# SOM.net
KiCad netlist of a schematic drawn in Altium Designer
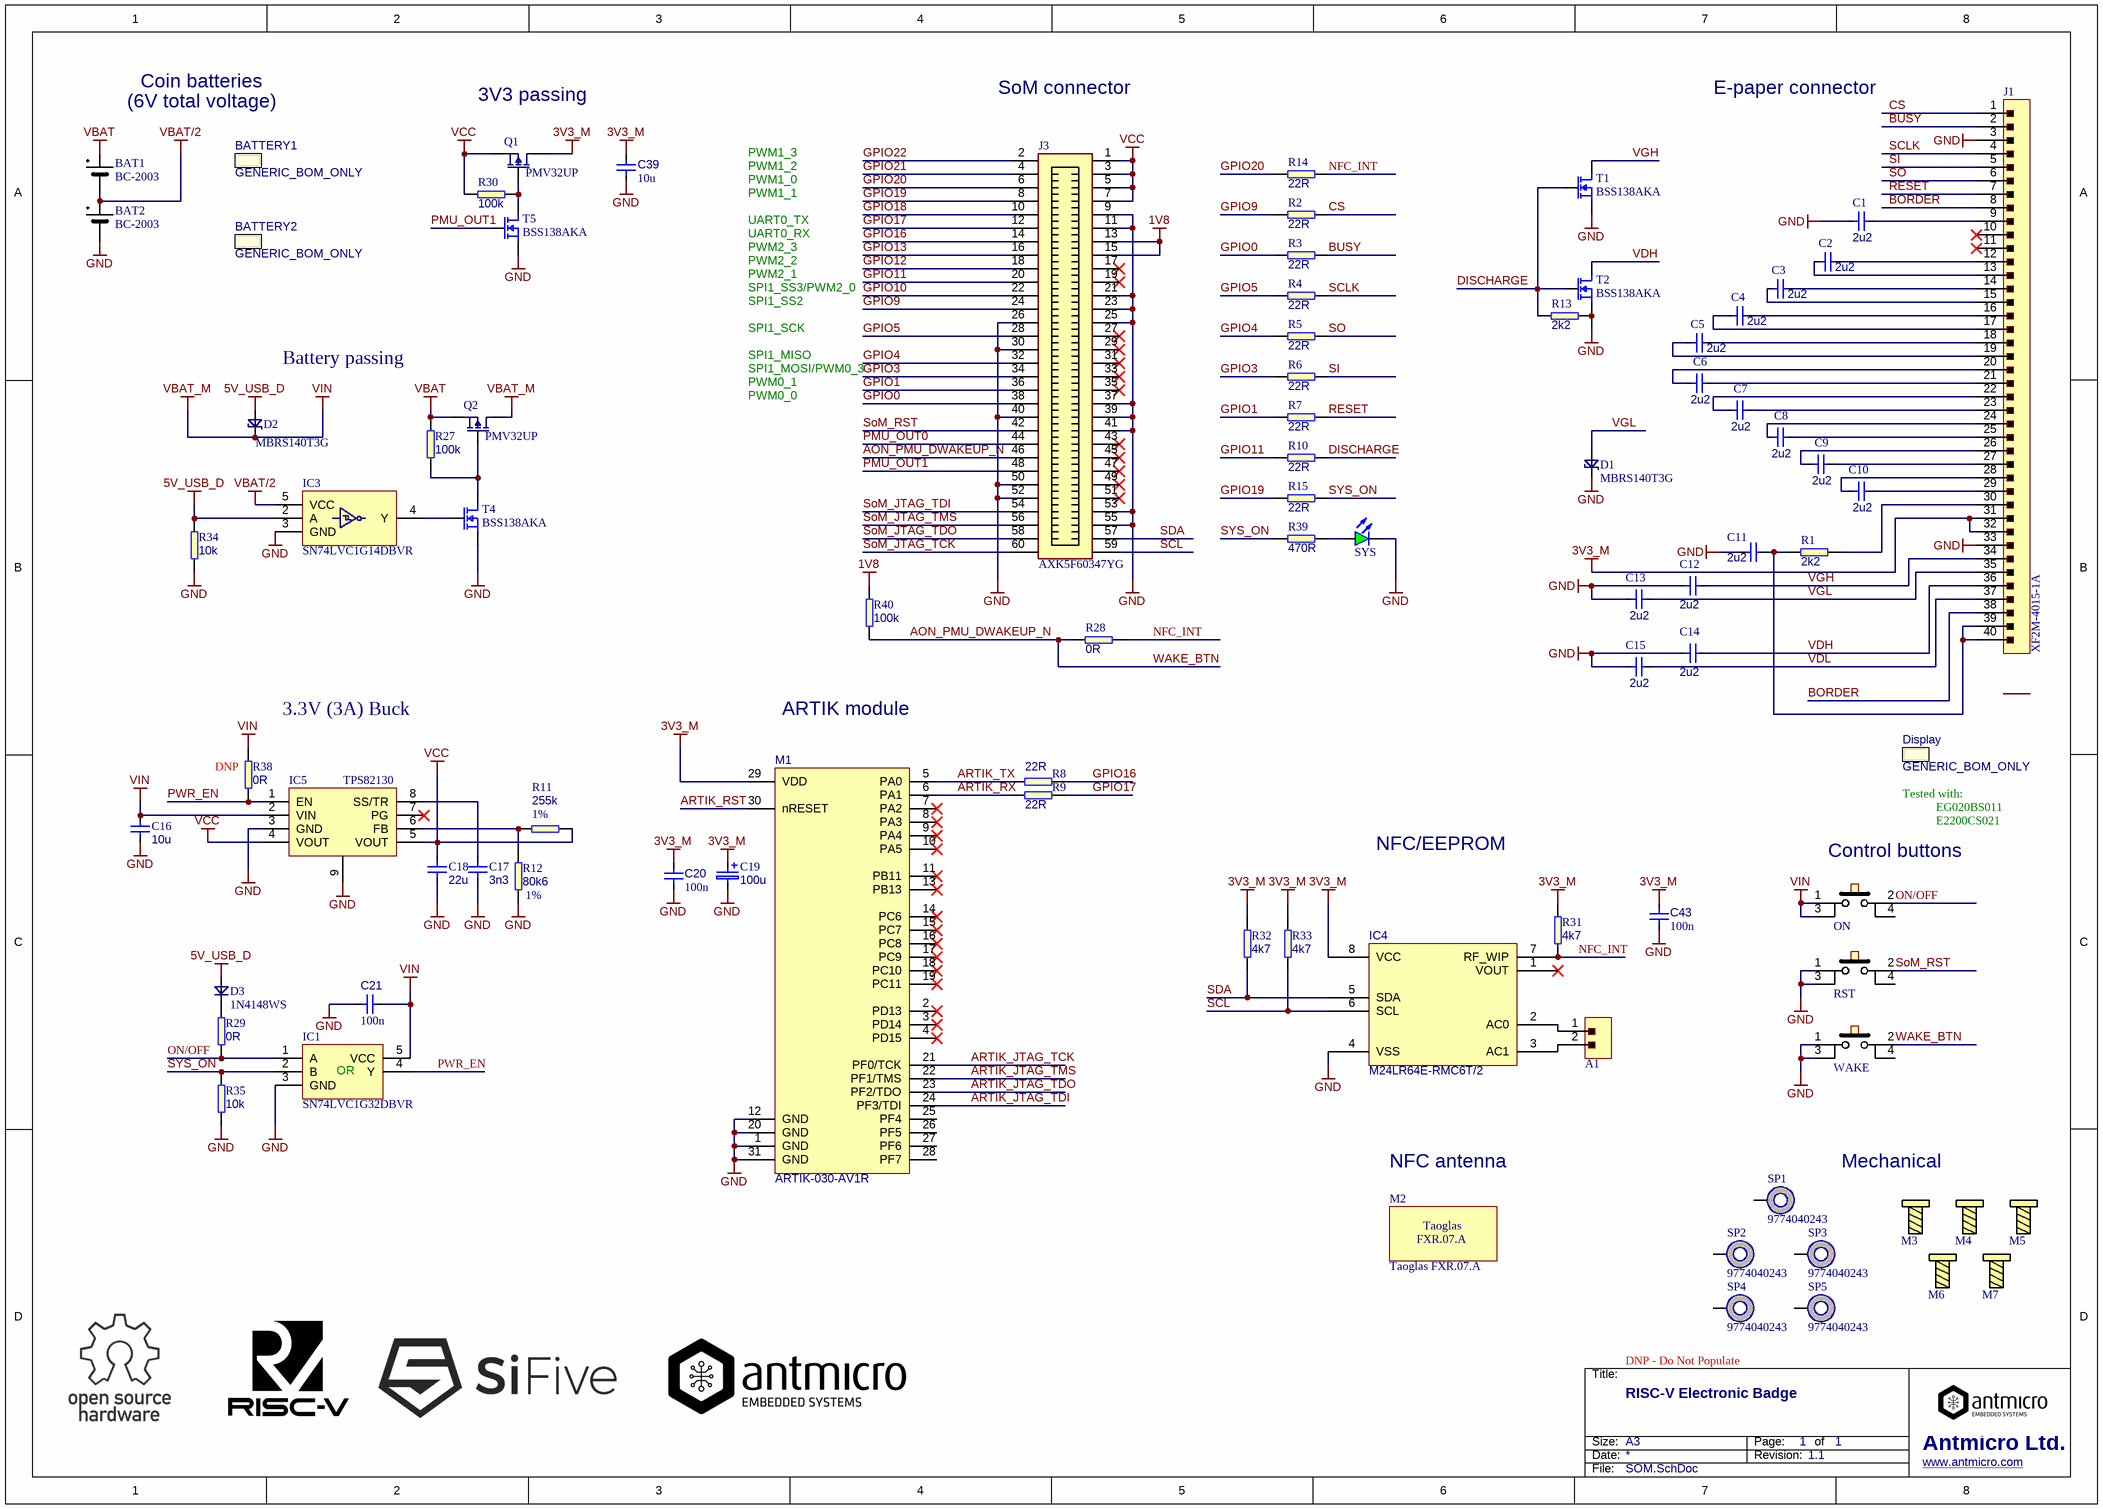
[diagram p0: SOM.SchDoc]

(export (version "E")
  (design (tool "Eeschema 10.0.6"))
  (components
    (comp (ref "A1")
      (value "811-22-002-30-001101")
      (footprint "812-22-002-30-003101")
      (description "Headers & Wire Housings 2P SINGLE ROW HDR .177\" PIN HEIGHT")
      (fields (field (name "MANUFACTURER") "MILL_MAX"))
      (libsource (lib "FE310_Badge") (part "1X02"))
    )
    (comp (ref "BAT1")
      (value "BC-2003")
      (footprint "BC-2003")
      (description "SMT holder for  CR2032 battery")
      (fields (field (name "MANUFACTURER") "Keystone"))
      (libsource (lib "FE310_Badge") (part "battery"))
    )
    (comp (ref "BAT2")
      (value "BC-2003")
      (footprint "BC-2003")
      (description "SMT holder for  CR2032 battery")
      (fields (field (name "MANUFACTURER") "Keystone"))
      (libsource (lib "FE310_Badge") (part "battery"))
    )
    (comp (ref "BATTERY1")
      (value "GENERIC_BOM_ONLY")
      (description "BOM Only")
      (fields (field (name "MANUFACTURER") "Pervasive Displays"))
      (libsource (lib "FE310_Badge") (part "GENERIC_BOM_ONLY"))
    )
    (comp (ref "BATTERY2")
      (value "GENERIC_BOM_ONLY")
      (description "BOM Only")
      (fields (field (name "MANUFACTURER") "Pervasive Displays"))
      (libsource (lib "FE310_Badge") (part "GENERIC_BOM_ONLY"))
    )
    (comp (ref "C1")
      (value "2u2")
      (footprint "0402")
      (description "MLCC SMT Capacitor 2u2 0402")
      (fields (field (name "PART NUMBER") "C_2u2_0402") (field (name "MANUFACTURER") "TDK"))
      (libsource (lib "FE310_Badge") (part "C_2u2_0402"))
    )
    (comp (ref "C2")
      (value "2u2")
      (footprint "0603")
      (description "MLCC SMT Capacitor 2u2 0603")
      (fields (field (name "PART NUMBER") "C_2u2_0603") (field (name "MANUFACTURER") "TDK"))
      (libsource (lib "FE310_Badge") (part "C_2u2_0603"))
    )
    (comp (ref "C3")
      (value "2u2")
      (footprint "0603")
      (description "MLCC SMT Capacitor 2u2 0603")
      (fields (field (name "PART NUMBER") "C_2u2_0603") (field (name "MANUFACTURER") "TDK"))
      (libsource (lib "FE310_Badge") (part "C_2u2_0603"))
    )
    (comp (ref "C4")
      (value "2u2")
      (footprint "0603")
      (description "MLCC SMT Capacitor 2u2 0603")
      (fields (field (name "PART NUMBER") "C_2u2_0603") (field (name "MANUFACTURER") "TDK"))
      (libsource (lib "FE310_Badge") (part "C_2u2_0603"))
    )
    (comp (ref "C5")
      (value "2u2")
      (footprint "0603")
      (description "MLCC SMT Capacitor 2u2 0603")
      (fields (field (name "PART NUMBER") "C_2u2_0603") (field (name "MANUFACTURER") "TDK"))
      (libsource (lib "FE310_Badge") (part "C_2u2_0603"))
    )
    (comp (ref "C6")
      (value "2u2")
      (footprint "0603")
      (description "MLCC SMT Capacitor 2u2 0603")
      (fields (field (name "PART NUMBER") "C_2u2_0603") (field (name "MANUFACTURER") "TDK"))
      (libsource (lib "FE310_Badge") (part "C_2u2_0603"))
    )
    (comp (ref "C7")
      (value "2u2")
      (footprint "0603")
      (description "MLCC SMT Capacitor 2u2 0603")
      (fields (field (name "PART NUMBER") "C_2u2_0603") (field (name "MANUFACTURER") "TDK"))
      (libsource (lib "FE310_Badge") (part "C_2u2_0603"))
    )
    (comp (ref "C8")
      (value "2u2")
      (footprint "0603")
      (description "MLCC SMT Capacitor 2u2 0603")
      (fields (field (name "PART NUMBER") "C_2u2_0603") (field (name "MANUFACTURER") "TDK"))
      (libsource (lib "FE310_Badge") (part "C_2u2_0603"))
    )
    (comp (ref "C9")
      (value "2u2")
      (footprint "0603")
      (description "MLCC SMT Capacitor 2u2 0603")
      (fields (field (name "PART NUMBER") "C_2u2_0603") (field (name "MANUFACTURER") "TDK"))
      (libsource (lib "FE310_Badge") (part "C_2u2_0603"))
    )
    (comp (ref "C10")
      (value "2u2")
      (footprint "0603")
      (description "MLCC SMT Capacitor 2u2 0603")
      (fields (field (name "PART NUMBER") "C_2u2_0603") (field (name "MANUFACTURER") "TDK"))
      (libsource (lib "FE310_Badge") (part "C_2u2_0603"))
    )
    (comp (ref "C11")
      (value "2u2")
      (footprint "0402")
      (description "MLCC SMT Capacitor 1u 0402")
      (fields (field (name "PART NUMBER") "C_2u2_0603") (field (name "MANUFACTURER") "MURATA"))
      (libsource (lib "FE310_Badge") (part "C_1u_0402"))
    )
    (comp (ref "C12")
      (value "2u2")
      (footprint "0603")
      (description "MLCC SMT Capacitor 2u2 0603")
      (fields (field (name "PART NUMBER") "C_2u2_0603") (field (name "MANUFACTURER") "TDK"))
      (libsource (lib "FE310_Badge") (part "C_2u2_0603"))
    )
    (comp (ref "C13")
      (value "2u2")
      (footprint "0603")
      (description "MLCC SMT Capacitor 2u2 0603")
      (fields (field (name "PART NUMBER") "C_2u2_0603") (field (name "MANUFACTURER") "TDK"))
      (libsource (lib "FE310_Badge") (part "C_2u2_0603"))
    )
    (comp (ref "C14")
      (value "2u2")
      (footprint "0603")
      (description "MLCC SMT Capacitor 2u2 0603")
      (fields (field (name "PART NUMBER") "C_2u2_0603") (field (name "MANUFACTURER") "TDK"))
      (libsource (lib "FE310_Badge") (part "C_2u2_0603"))
    )
    (comp (ref "C15")
      (value "2u2")
      (footprint "0603")
      (description "MLCC SMT Capacitor 2u2 0603")
      (fields (field (name "PART NUMBER") "C_2u2_0603") (field (name "MANUFACTURER") "TDK"))
      (libsource (lib "FE310_Badge") (part "C_2u2_0603"))
    )
    (comp (ref "C16")
      (value "10u")
      (footprint "0805")
      (description "MLCC SMT Capacitor 10u 0805")
      (fields (field (name "PART NUMBER") "C_10u_0805") (field (name "MANUFACTURER") "WALSIN"))
      (libsource (lib "FE310_Badge") (part "C_10u_0805"))
    )
    (comp (ref "C17")
      (value "3n3")
      (footprint "0603")
      (description "MLCC SMT Capacitor 3n3 0603")
      (fields (field (name "PART NUMBER") "C_3n3_0603") (field (name "MANUFACTURER") "WALSIN"))
      (libsource (lib "FE310_Badge") (part "C_3n3_0603"))
    )
    (comp (ref "C18")
      (value "22u")
      (footprint "0805")
      (description "MLCC SMT Capacitor 22u 0805")
      (fields (field (name "PART NUMBER") "C_22u_0805") (field (name "MANUFACTURER") "MULTICOMP"))
      (libsource (lib "FE310_Badge") (part "C_22u_0805"))
    )
    (comp (ref "C19")
      (value "100u")
      (footprint "KEMET_A")
      (description "Tantalum SMT Capacitor 100uF Case KEMET_A")
      (fields (field (name "PART NUMBER") "C_100u_KEMET_A") (field (name "MANUFACTURER") "VISHAY"))
      (libsource (lib "FE310_Badge") (part "CPol_100u"))
    )
    (comp (ref "C20")
      (value "100n")
      (footprint "0603")
      (description "MLCC SMT Capacitor 100nF 0603")
      (fields (field (name "PART NUMBER") "C_100n_0603") (field (name "MANUFACTURER") "WALSIN"))
      (libsource (lib "FE310_Badge") (part "C_100n_0603"))
    )
    (comp (ref "C21")
      (value "100n")
      (footprint "0402")
      (description "MLCC SMT Capacitor 100nF 0402")
      (fields (field (name "PART NUMBER") "C_100n_0402") (field (name "MANUFACTURER") "MULTICOMP"))
      (libsource (lib "FE310_Badge") (part "C_100n_0402"))
    )
    (comp (ref "C39")
      (value "10u")
      (footprint "0402")
      (description "MLCC SMT Capacitor 10uF 0402")
      (fields (field (name "PART NUMBER") "C_10u_0402") (field (name "MANUFACTURER") "TDK"))
      (libsource (lib "FE310_Badge") (part "C_10u_0402"))
    )
    (comp (ref "C43")
      (value "100n")
      (footprint "0402")
      (description "MLCC SMT Capacitor 100nF 0402")
      (fields (field (name "PART NUMBER") "C_100n_0402") (field (name "MANUFACTURER") "MULTICOMP"))
      (libsource (lib "FE310_Badge") (part "C_100n_0402"))
    )
    (comp (ref "D1")
      (value "MBRS140T3G")
      (footprint "SMB")
      (description "DIODE, SCHOTTKY, 1A, 40V, DO-214AA")
      (fields (field (name "MANUFACTURER") "ON SEMICONDUCTOR"))
      (libsource (lib "FE310_Badge") (part "Diode Schottky"))
    )
    (comp (ref "D2")
      (value "MBRS140T3G")
      (footprint "SMB")
      (description "DIODE, SCHOTTKY, 1A, 40V, DO-214AA")
      (fields (field (name "MANUFACTURER") "ON SEMICONDUCTOR"))
      (libsource (lib "FE310_Badge") (part "Diode Schottky"))
    )
    (comp (ref "D3")
      (value "1N4148WS")
      (footprint "SOD-323")
      (description "Diode small signal")
      (fields (field (name "MANUFACTURER") "MULTICOMP"))
      (libsource (lib "FE310_Badge") (part "diode"))
    )
    (comp (ref "Display")
      (value "GENERIC_BOM_ONLY")
      (description "BOM Only")
      (fields (field (name "MANUFACTURER") "Pervasive Displays"))
      (libsource (lib "FE310_Badge") (part "GENERIC_BOM_ONLY"))
    )
    (comp (ref "IC1")
      (value "SN74LVC1G32DBVR")
      (footprint "SOT23-5")
      (description "Single 2-Input OR Gate")
      (fields (field (name "MANUFACTURER") "TEXAS INSTRUMENTS"))
      (libsource (lib "FE310_Badge") (part "SN74LVC1G32DBVR"))
    )
    (comp (ref "IC3")
      (value "SN74LVC1G14DBVR")
      (footprint "SOT23-5")
      (description "Inverter with schmitt trigger.")
      (fields (field (name "MANUFACTURER") "TEXAS INSTRUMENTS"))
      (libsource (lib "FE310_Badge") (part "SN74LVC1G14"))
    )
    (comp (ref "IC4")
      (value "M24LR64E-RMC6T/2")
      (footprint "UFDFPN-8")
      (description "RFID Transponder IC 13.56MHz ISO 14443, NFC I²C 2.7 V ~ 5.5 V 8-UFDFN Exposed Pad")
      (fields (field (name "MANUFACTURER") "STMicroelectronics"))
      (libsource (lib "FE310_Badge") (part "M24LR04E_R"))
    )
    (comp (ref "IC5")
      (value "TPS82130")
      (footprint "MicroSIP")
      (fields (field (name "MANUFACTURER") "TEXAS INSTRUMENTS"))
      (libsource (lib "FE310_Badge") (part "TPS82130"))
    )
    (comp (ref "J1")
      (value "XF2M-4015-1A")
      (footprint "XF2M-4015-1A")
      (description "RECEPTACLE, FPC, ZIF, SMT, 0.5MM, 40WAY")
      (fields (field (name "MANUFACTURER") "OMRON ELECTRONIC COMPONENTS"))
      (libsource (lib "FE310_Badge") (part "XF2M-4015-1A"))
    )
    (comp (ref "J3")
      (value "AXK5F60347YG")
      (footprint "AXK5F60347YG")
      (description "CONN SCKT BRD/BRD .5MM 60POS SMD")
      (fields (field (name "MANUFACTURER") "PANASONIC"))
      (libsource (lib "FE310_Badge") (part "AXK5F60347YG"))
    )
    (comp (ref "M1")
      (value "ARTIK-030-AV1R")
      (footprint "ARTIK-030")
      (fields (field (name "PART NUMBER") "ARTIK-030") (field (name "MANUFACTURER") "Samsung"))
      (libsource (lib "FE310_Badge") (part "ARTIK-030"))
    )
    (comp (ref "M2")
      (value "Taoglas FXR.07.A")
      (description "ANT NFC FLEX CIRC 45.5X0.24MM")
      (fields (field (name "PART NUMBER") "taoglas") (field (name "MANUFACTURER") "TAOGLAS LIMITED"))
      (libsource (lib "FE310_Badge") (part "taoglas"))
    )
    (comp (ref "M3")
      (value "M2x5")
      (description "MACHINE SCREW PAN PHILLIPS M2")
      (fields
        (field (name "PART NUMBER") "MPMS 002 0005 PH")
        (field (name "MANUFACTURER") "B&F Fastener Supply")
      )
      (libsource (lib "FE310_Badge") (part "screw"))
    )
    (comp (ref "M4")
      (value "M2x5")
      (description "MACHINE SCREW PAN PHILLIPS M2")
      (fields
        (field (name "PART NUMBER") "MPMS 002 0005 PH")
        (field (name "MANUFACTURER") "B&F Fastener Supply")
      )
      (libsource (lib "FE310_Badge") (part "screw"))
    )
    (comp (ref "M5")
      (value "M2x5")
      (description "MACHINE SCREW PAN PHILLIPS M2")
      (fields
        (field (name "PART NUMBER") "MPMS 002 0005 PH")
        (field (name "MANUFACTURER") "B&F Fastener Supply")
      )
      (libsource (lib "FE310_Badge") (part "screw"))
    )
    (comp (ref "M6")
      (value "M2x5")
      (description "MACHINE SCREW PAN PHILLIPS M2")
      (fields
        (field (name "PART NUMBER") "MPMS 002 0005 PH")
        (field (name "MANUFACTURER") "B&F Fastener Supply")
      )
      (libsource (lib "FE310_Badge") (part "screw"))
    )
    (comp (ref "M7")
      (value "M2x5")
      (description "MACHINE SCREW PAN PHILLIPS M2")
      (fields
        (field (name "PART NUMBER") "MPMS 002 0005 PH")
        (field (name "MANUFACTURER") "B&F Fastener Supply")
      )
      (libsource (lib "FE310_Badge") (part "screw"))
    )
    (comp (ref "ON")
      (value "434333045822")
      (footprint "434333045822")
      (description "3.5x4.7 mm SMD side push, boss design WS-TASU")
      (fields (field (name "PART NUMBER") "WE_434333045822") (field (name "MANUFACTURER") "WURTH ELEKTRONIK"))
      (libsource (lib "FE310_Badge") (part "WE_434333045822"))
    )
    (comp (ref "Q1")
      (value "PMV32UP")
      (footprint "SOT-23")
      (description "P CH, 20V, 4A")
      (fields (field (name "MANUFACTURER") "NXP"))
      (libsource (lib "FE310_Badge") (part "PMOS"))
    )
    (comp (ref "Q2")
      (value "PMV32UP")
      (footprint "SOT-23")
      (description "P CH, 20V, 4A")
      (fields (field (name "MANUFACTURER") "NXP"))
      (libsource (lib "FE310_Badge") (part "PMOS"))
    )
    (comp (ref "R1")
      (value "2k2")
      (footprint "0402")
      (description "RES, 2k2, 0402")
      (fields (field (name "PART NUMBER") "R_2k2_0402") (field (name "MANUFACTURER") "MULTICOMP"))
      (libsource (lib "FE310_Badge") (part "R_2k2_0402"))
    )
    (comp (ref "R2")
      (value "22R")
      (footprint "0402")
      (description "RES, 22R, 0402")
      (fields (field (name "PART NUMBER") "R_22r_0402") (field (name "MANUFACTURER") "VISHAY"))
      (libsource (lib "FE310_Badge") (part "R_22R_0402"))
    )
    (comp (ref "R3")
      (value "22R")
      (footprint "0402")
      (description "RES, 22R, 0402")
      (fields (field (name "PART NUMBER") "R_22r_0402") (field (name "MANUFACTURER") "VISHAY"))
      (libsource (lib "FE310_Badge") (part "R_22R_0402"))
    )
    (comp (ref "R4")
      (value "22R")
      (footprint "0402")
      (description "RES, 22R, 0402")
      (fields (field (name "PART NUMBER") "R_22r_0402") (field (name "MANUFACTURER") "VISHAY"))
      (libsource (lib "FE310_Badge") (part "R_22R_0402"))
    )
    (comp (ref "R5")
      (value "22R")
      (footprint "0402")
      (description "RES, 22R, 0402")
      (fields (field (name "PART NUMBER") "R_22r_0402") (field (name "MANUFACTURER") "VISHAY"))
      (libsource (lib "FE310_Badge") (part "R_22R_0402"))
    )
    (comp (ref "R6")
      (value "22R")
      (footprint "0402")
      (description "RES, 22R, 0402")
      (fields (field (name "PART NUMBER") "R_22r_0402") (field (name "MANUFACTURER") "VISHAY"))
      (libsource (lib "FE310_Badge") (part "R_22R_0402"))
    )
    (comp (ref "R7")
      (value "22R")
      (footprint "0402")
      (description "RES, 22R, 0402")
      (fields (field (name "PART NUMBER") "R_22r_0402") (field (name "MANUFACTURER") "VISHAY"))
      (libsource (lib "FE310_Badge") (part "R_22R_0402"))
    )
    (comp (ref "R8")
      (value "22R")
      (footprint "0603")
      (description "RES, 22R, 0603")
      (fields (field (name "PART NUMBER") "R_22R_0603") (field (name "MANUFACTURER") "BOURNS"))
      (libsource (lib "FE310_Badge") (part "R_22R_0603"))
    )
    (comp (ref "R9")
      (value "22R")
      (footprint "0603")
      (description "RES, 22R, 0603")
      (fields (field (name "PART NUMBER") "R_22R_0603") (field (name "MANUFACTURER") "BOURNS"))
      (libsource (lib "FE310_Badge") (part "R_22R_0603"))
    )
    (comp (ref "R10")
      (value "22R")
      (footprint "0402")
      (description "RES, 22R, 0402")
      (fields (field (name "PART NUMBER") "R_22r_0402") (field (name "MANUFACTURER") "VISHAY"))
      (libsource (lib "FE310_Badge") (part "R_22R_0402"))
    )
    (comp (ref "R11")
      (value "255k")
      (footprint "0402")
      (description "RES, 255k 0402")
      (fields
        (field (name "PART NUMBER") "R_255k_0402")
        (field (name "MANUFACTURER") "PANASONIC")
        (field (name "TOLERANCE") "1%")
      )
      (libsource (lib "FE310_Badge") (part "R_255k_0402"))
    )
    (comp (ref "R12")
      (value "80k6")
      (footprint "0402")
      (description "RES, 80k6, 0402")
      (fields
        (field (name "PART NUMBER") "R_80k6_0402")
        (field (name "MANUFACTURER") "PANASONIC")
        (field (name "TOLERANCE") "1%")
      )
      (libsource (lib "FE310_Badge") (part "R_80k6_0402"))
    )
    (comp (ref "R13")
      (value "2k2")
      (footprint "0402")
      (description "RES, 2k2, 0402")
      (fields (field (name "PART NUMBER") "R_2k2_0402") (field (name "MANUFACTURER") "MULTICOMP"))
      (libsource (lib "FE310_Badge") (part "R_2k2_0402"))
    )
    (comp (ref "R14")
      (value "22R")
      (footprint "0402")
      (description "RES, 22R, 0402")
      (fields (field (name "PART NUMBER") "R_22r_0402") (field (name "MANUFACTURER") "VISHAY"))
      (libsource (lib "FE310_Badge") (part "R_22R_0402"))
    )
    (comp (ref "R15")
      (value "22R")
      (footprint "0402")
      (description "RES, 22R, 0402")
      (fields (field (name "PART NUMBER") "R_22r_0402") (field (name "MANUFACTURER") "VISHAY"))
      (libsource (lib "FE310_Badge") (part "R_22R_0402"))
    )
    (comp (ref "R27")
      (value "100k")
      (footprint "0402")
      (description "RES, 100k 0402")
      (fields (field (name "PART NUMBER") "R_100k_0402") (field (name "MANUFACTURER") "VISHAY"))
      (libsource (lib "FE310_Badge") (part "R_100k_0402"))
    )
    (comp (ref "R28")
      (value "0R")
      (footprint "0402")
      (description "RES, 0R, 0402")
      (fields (field (name "PART NUMBER") "R_0R_0402") (field (name "MANUFACTURER") "MULTICOMP"))
      (libsource (lib "FE310_Badge") (part "R_0R_0402"))
    )
    (comp (ref "R29")
      (value "0R")
      (footprint "0402")
      (description "RES, 0R, 0402")
      (fields (field (name "PART NUMBER") "R_0R_0402") (field (name "MANUFACTURER") "MULTICOMP"))
      (libsource (lib "") (part "R_0R_0402_1"))
    )
    (comp (ref "R30")
      (value "100k")
      (footprint "0402")
      (description "RES, 100k 0402")
      (fields (field (name "PART NUMBER") "R_100k_0402") (field (name "MANUFACTURER") "VISHAY"))
      (libsource (lib "") (part "R_100k_0402_1"))
    )
    (comp (ref "R31")
      (value "4k7")
      (footprint "0402")
      (description "RES, 4k7, 0402")
      (fields (field (name "PART NUMBER") "R_4k7_0402") (field (name "MANUFACTURER") "PANASONIC"))
      (libsource (lib "FE310_Badge") (part "R_4k7_0402"))
    )
    (comp (ref "R32")
      (value "4k7")
      (footprint "0402")
      (description "RES, 4k7, 0402")
      (fields (field (name "PART NUMBER") "R_4k7_0402") (field (name "MANUFACTURER") "PANASONIC"))
      (libsource (lib "FE310_Badge") (part "R_4k7_0402"))
    )
    (comp (ref "R33")
      (value "4k7")
      (footprint "0402")
      (description "RES, 4k7, 0402")
      (fields (field (name "PART NUMBER") "R_4k7_0402") (field (name "MANUFACTURER") "PANASONIC"))
      (libsource (lib "FE310_Badge") (part "R_4k7_0402"))
    )
    (comp (ref "R34")
      (value "10k")
      (footprint "0402")
      (description "RES, 10k, 0402")
      (fields (field (name "PART NUMBER") "R_10k_0402") (field (name "MANUFACTURER") "MULTICOMP"))
      (libsource (lib "FE310_Badge") (part "R_10k_0402"))
    )
    (comp (ref "R35")
      (value "10k")
      (footprint "0402")
      (description "RES, 10k, 0402")
      (fields (field (name "PART NUMBER") "R_10k_0402") (field (name "MANUFACTURER") "MULTICOMP"))
      (libsource (lib "FE310_Badge") (part "R_10k_0402"))
    )
    (comp (ref "R38")
      (value "0R")
      (footprint "0402")
      (description "RES, 0R, 0402")
      (fields (field (name "PART NUMBER") "R_0R_0402") (field (name "MANUFACTURER") "MULTICOMP"))
      (libsource (lib "") (part "R_0R_0402_1"))
    )
    (comp (ref "R39")
      (value "470R")
      (footprint "0603")
      (description "RES, 470R, 0603")
      (fields (field (name "PART NUMBER") "R_470R_0603") (field (name "MANUFACTURER") "BOURNS"))
      (libsource (lib "FE310_Badge") (part "R_470R_0603"))
    )
    (comp (ref "R40")
      (value "100k")
      (footprint "0402")
      (description "RES, 100k 0402")
      (fields (field (name "PART NUMBER") "R_100k_0402") (field (name "MANUFACTURER") "VISHAY"))
      (libsource (lib "FE310_Badge") (part "R_100k_0402"))
    )
    (comp (ref "RST")
      (value "434333045822")
      (footprint "434333045822")
      (description "3.5x4.7 mm SMD side push, boss design WS-TASU")
      (fields (field (name "PART NUMBER") "WE_434333045822") (field (name "MANUFACTURER") "WURTH ELEKTRONIK"))
      (libsource (lib "FE310_Badge") (part "WE_434333045822"))
    )
    (comp (ref "SP1")
      (value "9774040243")
      (footprint "M2-1mm")
      (description "M2x1.5")
      (fields (field (name "PART NUMBER") "WE_9774040243") (field (name "MANUFACTURER") "WURTH ELEKTRONIK"))
      (libsource (lib "FE310_Badge") (part "SPACER_1.5mm"))
    )
    (comp (ref "SP2")
      (value "9774040243")
      (footprint "M2-4mm")
      (description "M2x4")
      (fields (field (name "PART NUMBER") "WE_9774040243") (field (name "MANUFACTURER") "WURTH ELEKTRONIK"))
      (libsource (lib "FE310_Badge") (part "SPACER_4mm"))
    )
    (comp (ref "SP3")
      (value "9774040243")
      (footprint "M2-4mm")
      (description "M2x4")
      (fields (field (name "PART NUMBER") "WE_9774040243") (field (name "MANUFACTURER") "WURTH ELEKTRONIK"))
      (libsource (lib "FE310_Badge") (part "SPACER_4mm"))
    )
    (comp (ref "SP4")
      (value "9774040243")
      (footprint "M2-4mm")
      (description "M2x4")
      (fields (field (name "PART NUMBER") "WE_9774040243") (field (name "MANUFACTURER") "WURTH ELEKTRONIK"))
      (libsource (lib "FE310_Badge") (part "SPACER_4mm"))
    )
    (comp (ref "SP5")
      (value "9774040243")
      (footprint "M2-4mm")
      (description "M2x4")
      (fields (field (name "PART NUMBER") "WE_9774040243") (field (name "MANUFACTURER") "WURTH ELEKTRONIK"))
      (libsource (lib "FE310_Badge") (part "SPACER_4mm"))
    )
    (comp (ref "SYS")
      (value "KPT-1608SGC")
      (footprint "LED0603")
      (description "LED Green 0603 case")
      (fields (field (name "PART NUMBER") "LED_G") (field (name "MANUFACTURER") "KINGBRIGHT"))
      (libsource (lib "FE310_Badge") (part "LED"))
    )
    (comp (ref "T1")
      (value "BSS138AKA")
      (footprint "SOT-23")
      (description "MOSFET, N CH, 60V, 0.2A")
      (fields (field (name "PART NUMBER") "BSS138") (field (name "MANUFACTURER") "NXP"))
      (libsource (lib "FE310_Badge") (part "NMOS"))
    )
    (comp (ref "T2")
      (value "BSS138AKA")
      (footprint "SOT-23")
      (description "MOSFET, N CH, 60V, 0.2A")
      (fields (field (name "PART NUMBER") "BSS138") (field (name "MANUFACTURER") "NXP"))
      (libsource (lib "FE310_Badge") (part "NMOS"))
    )
    (comp (ref "T4")
      (value "BSS138AKA")
      (footprint "SOT-23")
      (description "MOSFET, N CH, 60V, 0.2A")
      (fields (field (name "PART NUMBER") "BSS138") (field (name "MANUFACTURER") "NXP"))
      (libsource (lib "FE310_Badge") (part "NMOS"))
    )
    (comp (ref "T5")
      (value "BSS138AKA")
      (footprint "SOT-23")
      (description "MOSFET, N CH, 60V, 0.2A")
      (fields (field (name "PART NUMBER") "BSS138") (field (name "MANUFACTURER") "NXP"))
      (libsource (lib "FE310_Badge") (part "NMOS"))
    )
    (comp (ref "WAKE")
      (value "434333045822")
      (footprint "434333045822")
      (description "3.5x4.7 mm SMD side push, boss design WS-TASU")
      (fields (field (name "PART NUMBER") "WE_434333045822") (field (name "MANUFACTURER") "WURTH ELEKTRONIK"))
      (libsource (lib "FE310_Badge") (part "WE_434333045822"))
    )
  )
  (nets
    (net (code "1") (name "/AON_PMU_DWAKEUP_N") (class "Default")
      (node (ref "J3") (pin "46") (pinfunction "46_46") (pintype "passive"))
      (node (ref "R28") (pin "1") (pintype "passive"))
      (node (ref "R40") (pin "1") (pintype "passive"))
      (node (ref "WAKE") (pin "2") (pinfunction "2_2") (pintype "passive"))
    )
    (net (code "2") (name "/ARTIK_JTAG_TCK") (class "Default")
      (node (ref "M1") (pin "21") (pinfunction "PF0/TCK_21") (pintype "passive"))
    )
    (net (code "3") (name "/ARTIK_JTAG_TDI") (class "Default")
      (node (ref "M1") (pin "24") (pinfunction "PF3/TDI_24") (pintype "passive"))
    )
    (net (code "4") (name "/ARTIK_JTAG_TDO") (class "Default")
      (node (ref "M1") (pin "23") (pinfunction "PF2/TDO_23") (pintype "passive"))
    )
    (net (code "5") (name "/ARTIK_JTAG_TMS") (class "Default")
      (node (ref "M1") (pin "22") (pinfunction "PF1/TMS_22") (pintype "passive"))
    )
    (net (code "6") (name "/ARTIK_RST") (class "Default")
      (node (ref "M1") (pin "30") (pinfunction "nRESET_30") (pintype "passive"))
    )
    (net (code "7") (name "/ARTIK_RX") (class "Default")
      (node (ref "M1") (pin "6") (pinfunction "PA1_6") (pintype "passive"))
      (node (ref "R9") (pin "1") (pintype "passive"))
    )
    (net (code "8") (name "/ARTIK_TX") (class "Default")
      (node (ref "M1") (pin "5") (pinfunction "PA0_5") (pintype "passive"))
      (node (ref "R8") (pin "1") (pintype "passive"))
    )
    (net (code "9") (name "/BORDER") (class "Default")
      (node (ref "J1") (pin "38") (pinfunction "38_38") (pintype "passive"))
      (node (ref "J1") (pin "8") (pinfunction "8_8") (pintype "passive"))
    )
    (net (code "10") (name "/BUSY") (class "Default")
      (node (ref "J1") (pin "2") (pinfunction "2_2") (pintype "passive"))
      (node (ref "R3") (pin "2") (pintype "passive"))
    )
    (net (code "11") (name "/CS") (class "Default")
      (node (ref "J1") (pin "1") (pinfunction "1_1") (pintype "passive"))
      (node (ref "R2") (pin "2") (pintype "passive"))
    )
    (net (code "12") (name "/DISCHARGE") (class "Default")
      (node (ref "R10") (pin "2") (pintype "passive"))
      (node (ref "R13") (pin "1") (pintype "passive"))
      (node (ref "T1") (pin "1") (pinfunction "G_1") (pintype "passive"))
      (node (ref "T2") (pin "1") (pinfunction "G_1") (pintype "passive"))
    )
    (net (code "13") (name "/GPIO0") (class "Default")
      (node (ref "J3") (pin "38") (pinfunction "38_38") (pintype "passive"))
      (node (ref "R3") (pin "1") (pintype "passive"))
    )
    (net (code "14") (name "/GPIO1") (class "Default")
      (node (ref "J3") (pin "36") (pinfunction "36_36") (pintype "passive"))
      (node (ref "R7") (pin "1") (pintype "passive"))
    )
    (net (code "15") (name "/GPIO3") (class "Default")
      (node (ref "J3") (pin "34") (pinfunction "34_34") (pintype "passive"))
      (node (ref "R6") (pin "1") (pintype "passive"))
    )
    (net (code "16") (name "/GPIO4") (class "Default")
      (node (ref "J3") (pin "32") (pinfunction "32_32") (pintype "passive"))
      (node (ref "R5") (pin "1") (pintype "passive"))
    )
    (net (code "17") (name "/GPIO5") (class "Default")
      (node (ref "J3") (pin "28") (pinfunction "28_28") (pintype "passive"))
      (node (ref "R4") (pin "1") (pintype "passive"))
    )
    (net (code "18") (name "/GPIO9") (class "Default")
      (node (ref "J3") (pin "24") (pinfunction "24_24") (pintype "passive"))
      (node (ref "R2") (pin "1") (pintype "passive"))
    )
    (net (code "19") (name "/GPIO10") (class "Default")
      (node (ref "J3") (pin "22") (pinfunction "22_22") (pintype "passive"))
    )
    (net (code "20") (name "/GPIO11") (class "Default")
      (node (ref "J3") (pin "20") (pinfunction "20_20") (pintype "passive"))
      (node (ref "R10") (pin "1") (pintype "passive"))
    )
    (net (code "21") (name "/GPIO12") (class "Default")
      (node (ref "J3") (pin "18") (pinfunction "18_18") (pintype "passive"))
    )
    (net (code "22") (name "/GPIO13") (class "Default")
      (node (ref "J3") (pin "16") (pinfunction "16_16") (pintype "passive"))
    )
    (net (code "23") (name "/GPIO16") (class "Default")
      (node (ref "J3") (pin "14") (pinfunction "14_14") (pintype "passive"))
      (node (ref "R8") (pin "2") (pintype "passive"))
    )
    (net (code "24") (name "/GPIO17") (class "Default")
      (node (ref "J3") (pin "12") (pinfunction "12_12") (pintype "passive"))
      (node (ref "R9") (pin "2") (pintype "passive"))
    )
    (net (code "25") (name "/GPIO18") (class "Default")
      (node (ref "J3") (pin "10") (pinfunction "10_10") (pintype "passive"))
    )
    (net (code "26") (name "/GPIO19") (class "Default")
      (node (ref "J3") (pin "8") (pinfunction "8_8") (pintype "passive"))
      (node (ref "R15") (pin "1") (pintype "passive"))
    )
    (net (code "27") (name "/GPIO20") (class "Default")
      (node (ref "J3") (pin "6") (pinfunction "6_6") (pintype "passive"))
      (node (ref "R14") (pin "1") (pintype "passive"))
    )
    (net (code "28") (name "/GPIO21") (class "Default")
      (node (ref "J3") (pin "4") (pinfunction "4_4") (pintype "passive"))
    )
    (net (code "29") (name "/GPIO22") (class "Default")
      (node (ref "J3") (pin "2") (pinfunction "2_2") (pintype "passive"))
    )
    (net (code "30") (name "/NFC_INT") (class "Default")
      (node (ref "IC4") (pin "7") (pinfunction "RF_WIP_7") (pintype "passive"))
      (node (ref "R14") (pin "2") (pintype "passive"))
      (node (ref "R28") (pin "2") (pintype "passive"))
      (node (ref "R31") (pin "1") (pintype "passive"))
    )
    (net (code "31") (name "/ON{slash}OFF") (class "Default")
      (node (ref "IC1") (pin "1") (pinfunction "A_1") (pintype "passive"))
      (node (ref "ON") (pin "2") (pinfunction "2_2") (pintype "passive"))
      (node (ref "R29") (pin "1") (pintype "passive"))
    )
    (net (code "32") (name "/PMU_OUT0") (class "Default")
      (node (ref "J3") (pin "44") (pinfunction "44_44") (pintype "passive"))
    )
    (net (code "33") (name "/PMU_OUT1") (class "Default")
      (node (ref "J3") (pin "48") (pinfunction "48_48") (pintype "passive"))
      (node (ref "T5") (pin "1") (pinfunction "G_1") (pintype "passive"))
    )
    (net (code "34") (name "/PWR_EN") (class "Default")
      (node (ref "IC1") (pin "4") (pinfunction "Y_4") (pintype "passive"))
      (node (ref "IC5") (pin "1") (pinfunction "EN_1") (pintype "passive"))
      (node (ref "R38") (pin "1") (pintype "passive"))
    )
    (net (code "35") (name "/RESET") (class "Default")
      (node (ref "J1") (pin "7") (pinfunction "7_7") (pintype "passive"))
      (node (ref "R7") (pin "2") (pintype "passive"))
    )
    (net (code "36") (name "/SCL") (class "Default")
      (node (ref "IC4") (pin "6") (pinfunction "SCL_6") (pintype "passive"))
      (node (ref "J3") (pin "59") (pinfunction "59_59") (pintype "passive"))
      (node (ref "R33") (pin "1") (pintype "passive"))
    )
    (net (code "37") (name "/SCLK") (class "Default")
      (node (ref "J1") (pin "4") (pinfunction "4_4") (pintype "passive"))
      (node (ref "R4") (pin "2") (pintype "passive"))
    )
    (net (code "38") (name "/SDA") (class "Default")
      (node (ref "IC4") (pin "5") (pinfunction "SDA_5") (pintype "passive"))
      (node (ref "J3") (pin "57") (pinfunction "57_57") (pintype "passive"))
      (node (ref "R32") (pin "1") (pintype "passive"))
    )
    (net (code "39") (name "/SI") (class "Default")
      (node (ref "J1") (pin "5") (pinfunction "5_5") (pintype "passive"))
      (node (ref "R6") (pin "2") (pintype "passive"))
    )
    (net (code "40") (name "/SO") (class "Default")
      (node (ref "J1") (pin "6") (pinfunction "6_6") (pintype "passive"))
      (node (ref "R5") (pin "2") (pintype "passive"))
    )
    (net (code "41") (name "/SYS_ON") (class "Default")
      (node (ref "IC1") (pin "2") (pinfunction "B_2") (pintype "passive"))
      (node (ref "R15") (pin "2") (pintype "passive"))
      (node (ref "R35") (pin "2") (pintype "passive"))
      (node (ref "R39") (pin "2") (pintype "passive"))
    )
    (net (code "42") (name "/SoM_JTAG_TCK") (class "Default")
      (node (ref "J3") (pin "60") (pinfunction "60_60") (pintype "passive"))
    )
    (net (code "43") (name "/SoM_JTAG_TDI") (class "Default")
      (node (ref "J3") (pin "54") (pinfunction "54_54") (pintype "passive"))
    )
    (net (code "44") (name "/SoM_JTAG_TDO") (class "Default")
      (node (ref "J3") (pin "58") (pinfunction "58_58") (pintype "passive"))
    )
    (net (code "45") (name "/SoM_JTAG_TMS") (class "Default")
      (node (ref "J3") (pin "56") (pinfunction "56_56") (pintype "passive"))
    )
    (net (code "46") (name "/SoM_RST") (class "Default")
      (node (ref "J3") (pin "42") (pinfunction "42_42") (pintype "passive"))
      (node (ref "RST") (pin "2") (pinfunction "2_2") (pintype "passive"))
    )
    (net (code "47") (name "/VDH") (class "Default")
      (node (ref "C14") (pin "2") (pinfunction "2_2") (pintype "passive"))
      (node (ref "J1") (pin "36") (pinfunction "36_36") (pintype "passive"))
      (node (ref "T2") (pin "3") (pinfunction "D_3") (pintype "passive"))
    )
    (net (code "48") (name "/VDL") (class "Default")
      (node (ref "C15") (pin "2") (pinfunction "2_2") (pintype "passive"))
      (node (ref "J1") (pin "37") (pinfunction "37_37") (pintype "passive"))
    )
    (net (code "49") (name "/VGH") (class "Default")
      (node (ref "C12") (pin "2") (pinfunction "2_2") (pintype "passive"))
      (node (ref "J1") (pin "34") (pinfunction "34_34") (pintype "passive"))
      (node (ref "T1") (pin "3") (pinfunction "D_3") (pintype "passive"))
    )
    (net (code "50") (name "/VGL") (class "Default")
      (node (ref "C13") (pin "2") (pinfunction "2_2") (pintype "passive"))
      (node (ref "D1") (pin "A") (pinfunction "A_A") (pintype "passive"))
      (node (ref "J1") (pin "35") (pinfunction "35_35") (pintype "passive"))
    )
    (net (code "51") (name "1V8") (class "Default")
      (node (ref "J3") (pin "13") (pinfunction "13_13") (pintype "passive"))
      (node (ref "J3") (pin "15") (pinfunction "15_15") (pintype "passive"))
      (node (ref "R40") (pin "2") (pintype "passive"))
    )
    (net (code "52") (name "3V3_M") (class "Default")
      (node (ref "C19") (pin "1") (pinfunction "1_1") (pintype "passive"))
      (node (ref "C20") (pin "2") (pinfunction "2_2") (pintype "passive"))
      (node (ref "C39") (pin "2") (pinfunction "2_2") (pintype "passive"))
      (node (ref "C43") (pin "1") (pinfunction "1_1") (pintype "passive"))
      (node (ref "IC4") (pin "8") (pinfunction "VCC_8") (pintype "passive"))
      (node (ref "J1") (pin "31") (pinfunction "31_31") (pintype "passive"))
      (node (ref "J1") (pin "32") (pinfunction "32_32") (pintype "passive"))
      (node (ref "M1") (pin "29") (pinfunction "VDD_29") (pintype "passive"))
      (node (ref "Q1") (pin "3") (pinfunction "D_3") (pintype "passive"))
      (node (ref "R31") (pin "2") (pintype "passive"))
      (node (ref "R32") (pin "2") (pintype "passive"))
      (node (ref "R33") (pin "2") (pintype "passive"))
    )
    (net (code "53") (name "5V_USB_D") (class "Default")
      (node (ref "D2") (pin "A") (pinfunction "A_A") (pintype "passive"))
      (node (ref "D3") (pin "A") (pinfunction "A_A") (pintype "passive"))
      (node (ref "IC3") (pin "2") (pinfunction "A_2") (pintype "passive"))
      (node (ref "R34") (pin "2") (pintype "passive"))
    )
    (net (code "54") (name "GND") (class "Default")
      (node (ref "BAT2") (pin "-") (pinfunction "-_-") (pintype "passive"))
      (node (ref "C1") (pin "1") (pinfunction "1_1") (pintype "passive"))
      (node (ref "C11") (pin "1") (pinfunction "1_1") (pintype "passive"))
      (node (ref "C12") (pin "1") (pinfunction "1_1") (pintype "passive"))
      (node (ref "C13") (pin "1") (pinfunction "1_1") (pintype "passive"))
      (node (ref "C14") (pin "1") (pinfunction "1_1") (pintype "passive"))
      (node (ref "C15") (pin "1") (pinfunction "1_1") (pintype "passive"))
      (node (ref "C16") (pin "1") (pinfunction "1_1") (pintype "passive"))
      (node (ref "C17") (pin "1") (pinfunction "1_1") (pintype "passive"))
      (node (ref "C18") (pin "1") (pinfunction "1_1") (pintype "passive"))
      (node (ref "C19") (pin "2") (pinfunction "2_2") (pintype "passive"))
      (node (ref "C20") (pin "1") (pinfunction "1_1") (pintype "passive"))
      (node (ref "C21") (pin "1") (pinfunction "1_1") (pintype "passive"))
      (node (ref "C39") (pin "1") (pinfunction "1_1") (pintype "passive"))
      (node (ref "C43") (pin "2") (pinfunction "2_2") (pintype "passive"))
      (node (ref "D1") (pin "C") (pinfunction "C_C") (pintype "passive"))
      (node (ref "IC1") (pin "3") (pinfunction "GND_3") (pintype "passive"))
      (node (ref "IC3") (pin "3") (pinfunction "GND_3") (pintype "passive"))
      (node (ref "IC4") (pin "4") (pinfunction "VSS_4") (pintype "passive"))
      (node (ref "IC5") (pin "3") (pinfunction "GND_3") (pintype "passive"))
      (node (ref "IC5") (pin "9") (pinfunction "GND_9") (pintype "passive"))
      (node (ref "J1") (pin "3") (pinfunction "3_3") (pintype "passive"))
      (node (ref "J1") (pin "33") (pinfunction "33_33") (pintype "passive"))
      (node (ref "J3") (pin "11") (pinfunction "11_11") (pintype "passive"))
      (node (ref "J3") (pin "21") (pinfunction "21_21") (pintype "passive"))
      (node (ref "J3") (pin "23") (pinfunction "23_23") (pintype "passive"))
      (node (ref "J3") (pin "25") (pinfunction "25_25") (pintype "passive"))
      (node (ref "J3") (pin "26") (pinfunction "26_26") (pintype "passive"))
      (node (ref "J3") (pin "30") (pinfunction "30_30") (pintype "passive"))
      (node (ref "J3") (pin "37") (pinfunction "37_37") (pintype "passive"))
      (node (ref "J3") (pin "39") (pinfunction "39_39") (pintype "passive"))
      (node (ref "J3") (pin "40") (pinfunction "40_40") (pintype "passive"))
      (node (ref "J3") (pin "41") (pinfunction "41_41") (pintype "passive"))
      (node (ref "J3") (pin "50") (pinfunction "50_50") (pintype "passive"))
      (node (ref "J3") (pin "52") (pinfunction "52_52") (pintype "passive"))
      (node (ref "J3") (pin "53") (pinfunction "53_53") (pintype "passive"))
      (node (ref "J3") (pin "55") (pinfunction "55_55") (pintype "passive"))
      (node (ref "J3") (pin "9") (pinfunction "9_9") (pintype "passive"))
      (node (ref "M1") (pin "1") (pinfunction "GND_1") (pintype "passive"))
      (node (ref "M1") (pin "12") (pinfunction "GND_12") (pintype "passive"))
      (node (ref "M1") (pin "20") (pinfunction "GND_20") (pintype "passive"))
      (node (ref "M1") (pin "31") (pinfunction "GND_31") (pintype "passive"))
      (node (ref "R12") (pin "2") (pintype "passive"))
      (node (ref "R13") (pin "2") (pintype "passive"))
      (node (ref "R34") (pin "1") (pintype "passive"))
      (node (ref "R35") (pin "1") (pintype "passive"))
      (node (ref "RST") (pin "1") (pinfunction "1_1") (pintype "passive"))
      (node (ref "RST") (pin "3") (pinfunction "3_3") (pintype "passive"))
      (node (ref "SYS") (pin "K") (pinfunction "K_K") (pintype "passive"))
      (node (ref "T1") (pin "2") (pinfunction "S_2") (pintype "passive"))
      (node (ref "T2") (pin "2") (pinfunction "S_2") (pintype "passive"))
      (node (ref "T4") (pin "2") (pinfunction "S_2") (pintype "passive"))
      (node (ref "T5") (pin "2") (pinfunction "S_2") (pintype "passive"))
      (node (ref "WAKE") (pin "1") (pinfunction "1_1") (pintype "passive"))
      (node (ref "WAKE") (pin "3") (pinfunction "3_3") (pintype "passive"))
    )
    (net (code "55") (name "Net-(C1-Pad2)") (class "Default")
      (node (ref "C1") (pin "2") (pinfunction "2_2") (pintype "passive"))
      (node (ref "J1") (pin "9") (pinfunction "9_9") (pintype "passive"))
    )
    (net (code "56") (name "Net-(C2-Pad1)") (class "Default")
      (node (ref "C2") (pin "1") (pinfunction "1_1") (pintype "passive"))
      (node (ref "J1") (pin "13") (pinfunction "13_13") (pintype "passive"))
    )
    (net (code "57") (name "Net-(C2-Pad2)") (class "Default")
      (node (ref "C2") (pin "2") (pinfunction "2_2") (pintype "passive"))
      (node (ref "J1") (pin "12") (pinfunction "12_12") (pintype "passive"))
    )
    (net (code "58") (name "Net-(C3-Pad1)") (class "Default")
      (node (ref "C3") (pin "1") (pinfunction "1_1") (pintype "passive"))
      (node (ref "J1") (pin "15") (pinfunction "15_15") (pintype "passive"))
    )
    (net (code "59") (name "Net-(C3-Pad2)") (class "Default")
      (node (ref "C3") (pin "2") (pinfunction "2_2") (pintype "passive"))
      (node (ref "J1") (pin "14") (pinfunction "14_14") (pintype "passive"))
    )
    (net (code "60") (name "Net-(C4-Pad1)") (class "Default")
      (node (ref "C4") (pin "1") (pinfunction "1_1") (pintype "passive"))
      (node (ref "J1") (pin "17") (pinfunction "17_17") (pintype "passive"))
    )
    (net (code "61") (name "Net-(C4-Pad2)") (class "Default")
      (node (ref "C4") (pin "2") (pinfunction "2_2") (pintype "passive"))
      (node (ref "J1") (pin "16") (pinfunction "16_16") (pintype "passive"))
    )
    (net (code "62") (name "Net-(C5-Pad1)") (class "Default")
      (node (ref "C5") (pin "1") (pinfunction "1_1") (pintype "passive"))
      (node (ref "J1") (pin "19") (pinfunction "19_19") (pintype "passive"))
    )
    (net (code "63") (name "Net-(C5-Pad2)") (class "Default")
      (node (ref "C5") (pin "2") (pinfunction "2_2") (pintype "passive"))
      (node (ref "J1") (pin "18") (pinfunction "18_18") (pintype "passive"))
    )
    (net (code "64") (name "Net-(C6-Pad1)") (class "Default")
      (node (ref "C6") (pin "1") (pinfunction "1_1") (pintype "passive"))
      (node (ref "J1") (pin "20") (pinfunction "20_20") (pintype "passive"))
    )
    (net (code "65") (name "Net-(C6-Pad2)") (class "Default")
      (node (ref "C6") (pin "2") (pinfunction "2_2") (pintype "passive"))
      (node (ref "J1") (pin "21") (pinfunction "21_21") (pintype "passive"))
    )
    (net (code "66") (name "Net-(C7-Pad1)") (class "Default")
      (node (ref "C7") (pin "1") (pinfunction "1_1") (pintype "passive"))
      (node (ref "J1") (pin "22") (pinfunction "22_22") (pintype "passive"))
    )
    (net (code "67") (name "Net-(C7-Pad2)") (class "Default")
      (node (ref "C7") (pin "2") (pinfunction "2_2") (pintype "passive"))
      (node (ref "J1") (pin "23") (pinfunction "23_23") (pintype "passive"))
    )
    (net (code "68") (name "Net-(C8-Pad1)") (class "Default")
      (node (ref "C8") (pin "1") (pinfunction "1_1") (pintype "passive"))
      (node (ref "J1") (pin "24") (pinfunction "24_24") (pintype "passive"))
    )
    (net (code "69") (name "Net-(C8-Pad2)") (class "Default")
      (node (ref "C8") (pin "2") (pinfunction "2_2") (pintype "passive"))
      (node (ref "J1") (pin "25") (pinfunction "25_25") (pintype "passive"))
    )
    (net (code "70") (name "Net-(C9-Pad1)") (class "Default")
      (node (ref "C9") (pin "1") (pinfunction "1_1") (pintype "passive"))
      (node (ref "J1") (pin "26") (pinfunction "26_26") (pintype "passive"))
    )
    (net (code "71") (name "Net-(C9-Pad2)") (class "Default")
      (node (ref "C9") (pin "2") (pinfunction "2_2") (pintype "passive"))
      (node (ref "J1") (pin "27") (pinfunction "27_27") (pintype "passive"))
    )
    (net (code "72") (name "Net-(C10-Pad1)") (class "Default")
      (node (ref "C10") (pin "1") (pinfunction "1_1") (pintype "passive"))
      (node (ref "J1") (pin "28") (pinfunction "28_28") (pintype "passive"))
    )
    (net (code "73") (name "Net-(C10-Pad2)") (class "Default")
      (node (ref "C10") (pin "2") (pinfunction "2_2") (pintype "passive"))
      (node (ref "J1") (pin "29") (pinfunction "29_29") (pintype "passive"))
    )
    (net (code "74") (name "Net-(C11-Pad2)") (class "Default")
      (node (ref "C11") (pin "2") (pinfunction "2_2") (pintype "passive"))
      (node (ref "J1") (pin "39") (pinfunction "39_39") (pintype "passive"))
      (node (ref "J1") (pin "40") (pinfunction "40_40") (pintype "passive"))
      (node (ref "R1") (pin "1") (pintype "passive"))
    )
    (net (code "75") (name "Net-(D3-PadC)") (class "Default")
      (node (ref "D3") (pin "C") (pinfunction "C_C") (pintype "passive"))
      (node (ref "R29") (pin "2") (pintype "passive"))
    )
    (net (code "76") (name "Net-(IC3-Y)") (class "Default")
      (node (ref "IC3") (pin "4") (pinfunction "Y_4") (pintype "passive"))
      (node (ref "T4") (pin "1") (pinfunction "G_1") (pintype "passive"))
    )
    (net (code "77") (name "Net-(IC4-AC0)") (class "Default")
      (node (ref "A1") (pin "1") (pinfunction "1_1") (pintype "passive"))
      (node (ref "IC4") (pin "2") (pinfunction "AC0_2") (pintype "passive"))
    )
    (net (code "78") (name "Net-(IC4-AC1)") (class "Default")
      (node (ref "A1") (pin "2") (pinfunction "2_2") (pintype "passive"))
      (node (ref "IC4") (pin "3") (pinfunction "AC1_3") (pintype "passive"))
    )
    (net (code "79") (name "Net-(IC5-FB)") (class "Default")
      (node (ref "IC5") (pin "6") (pinfunction "FB_6") (pintype "passive"))
      (node (ref "R11") (pin "1") (pintype "passive"))
      (node (ref "R12") (pin "1") (pintype "passive"))
    )
    (net (code "80") (name "Net-(IC5-SS{slash}TR)") (class "Default")
      (node (ref "C17") (pin "2") (pinfunction "2_2") (pintype "passive"))
      (node (ref "IC5") (pin "8") (pinfunction "SS/TR_8") (pintype "passive"))
    )
    (net (code "81") (name "Net-(J1-Pad30)") (class "Default")
      (node (ref "J1") (pin "30") (pinfunction "30_30") (pintype "passive"))
      (node (ref "R1") (pin "2") (pintype "passive"))
    )
    (net (code "82") (name "Net-(Q1-G)") (class "Default")
      (node (ref "Q1") (pin "1") (pinfunction "G_1") (pintype "passive"))
      (node (ref "R30") (pin "2") (pintype "passive"))
      (node (ref "T5") (pin "3") (pinfunction "D_3") (pintype "passive"))
    )
    (net (code "83") (name "Net-(Q2-G)") (class "Default")
      (node (ref "Q2") (pin "1") (pinfunction "G_1") (pintype "passive"))
      (node (ref "R27") (pin "1") (pintype "passive"))
      (node (ref "T4") (pin "3") (pinfunction "D_3") (pintype "passive"))
    )
    (net (code "84") (name "Net-(R39-Pad1)") (class "Default")
      (node (ref "R39") (pin "1") (pintype "passive"))
      (node (ref "SYS") (pin "A") (pinfunction "A_A") (pintype "passive"))
    )
    (net (code "85") (name "VBAT") (class "Default")
      (node (ref "BAT1") (pin "+") (pinfunction "+_+") (pintype "passive"))
      (node (ref "Q2") (pin "2") (pinfunction "S_2") (pintype "passive"))
      (node (ref "R27") (pin "2") (pintype "passive"))
    )
    (net (code "86") (name "VBAT_M") (class "Default")
      (node (ref "C16") (pin "2") (pinfunction "2_2") (pintype "passive"))
      (node (ref "C21") (pin "2") (pinfunction "2_2") (pintype "passive"))
      (node (ref "D2") (pin "C") (pinfunction "C_C") (pintype "passive"))
      (node (ref "IC1") (pin "5") (pinfunction "VCC_5") (pintype "passive"))
      (node (ref "IC5") (pin "2") (pinfunction "VIN_2") (pintype "passive"))
      (node (ref "ON") (pin "1") (pinfunction "1_1") (pintype "passive"))
      (node (ref "ON") (pin "3") (pinfunction "3_3") (pintype "passive"))
      (node (ref "Q2") (pin "3") (pinfunction "D_3") (pintype "passive"))
      (node (ref "R38") (pin "2") (pintype "passive"))
    )
    (net (code "87") (name "VBAT{slash}2") (class "Default")
      (node (ref "BAT1") (pin "-") (pinfunction "-_-") (pintype "passive"))
      (node (ref "BAT2") (pin "+") (pinfunction "+_+") (pintype "passive"))
      (node (ref "IC3") (pin "5") (pinfunction "VCC_5") (pintype "passive"))
    )
    (net (code "88") (name "VCC") (class "Default")
      (node (ref "C18") (pin "2") (pinfunction "2_2") (pintype "passive"))
      (node (ref "IC5") (pin "4") (pinfunction "VOUT_4") (pintype "passive"))
      (node (ref "IC5") (pin "5") (pinfunction "VOUT_5") (pintype "passive"))
      (node (ref "J3") (pin "1") (pinfunction "1_1") (pintype "passive"))
      (node (ref "J3") (pin "3") (pinfunction "3_3") (pintype "passive"))
      (node (ref "J3") (pin "5") (pinfunction "5_5") (pintype "passive"))
      (node (ref "J3") (pin "7") (pinfunction "7_7") (pintype "passive"))
      (node (ref "Q1") (pin "2") (pinfunction "S_2") (pintype "passive"))
      (node (ref "R11") (pin "2") (pintype "passive"))
      (node (ref "R30") (pin "1") (pintype "passive"))
    )
    (net (code "89") (name "unconnected-(IC4-VOUT-Pad1)") (class "Default")
      (node (ref "IC4") (pin "1") (pinfunction "VOUT_1") (pintype "passive+no_connect"))
    )
    (net (code "90") (name "unconnected-(IC5-PG-Pad7)") (class "Default")
      (node (ref "IC5") (pin "7") (pinfunction "PG_7") (pintype "passive+no_connect"))
    )
    (net (code "91") (name "unconnected-(J1-Pad10)") (class "Default")
      (node (ref "J1") (pin "10") (pinfunction "10_10") (pintype "passive+no_connect"))
    )
    (net (code "92") (name "unconnected-(J1-Pad11)") (class "Default")
      (node (ref "J1") (pin "11") (pinfunction "11_11") (pintype "passive+no_connect"))
    )
    (net (code "93") (name "unconnected-(J3-Pad17)") (class "Default")
      (node (ref "J3") (pin "17") (pinfunction "17_17") (pintype "passive+no_connect"))
    )
    (net (code "94") (name "unconnected-(J3-Pad19)") (class "Default")
      (node (ref "J3") (pin "19") (pinfunction "19_19") (pintype "passive+no_connect"))
    )
    (net (code "95") (name "unconnected-(J3-Pad27)") (class "Default")
      (node (ref "J3") (pin "27") (pinfunction "27_27") (pintype "passive+no_connect"))
    )
    (net (code "96") (name "unconnected-(J3-Pad29)") (class "Default")
      (node (ref "J3") (pin "29") (pinfunction "29_29") (pintype "passive+no_connect"))
    )
    (net (code "97") (name "unconnected-(J3-Pad31)") (class "Default")
      (node (ref "J3") (pin "31") (pinfunction "31_31") (pintype "passive+no_connect"))
    )
    (net (code "98") (name "unconnected-(J3-Pad33)") (class "Default")
      (node (ref "J3") (pin "33") (pinfunction "33_33") (pintype "passive+no_connect"))
    )
    (net (code "99") (name "unconnected-(J3-Pad35)") (class "Default")
      (node (ref "J3") (pin "35") (pinfunction "35_35") (pintype "passive+no_connect"))
    )
    (net (code "100") (name "unconnected-(J3-Pad43)") (class "Default")
      (node (ref "J3") (pin "43") (pinfunction "43_43") (pintype "passive+no_connect"))
    )
    (net (code "101") (name "unconnected-(J3-Pad45)") (class "Default")
      (node (ref "J3") (pin "45") (pinfunction "45_45") (pintype "passive+no_connect"))
    )
    (net (code "102") (name "unconnected-(J3-Pad47)") (class "Default")
      (node (ref "J3") (pin "47") (pinfunction "47_47") (pintype "passive+no_connect"))
    )
    (net (code "103") (name "unconnected-(J3-Pad49)") (class "Default")
      (node (ref "J3") (pin "49") (pinfunction "49_49") (pintype "passive+no_connect"))
    )
    (net (code "104") (name "unconnected-(J3-Pad51)") (class "Default")
      (node (ref "J3") (pin "51") (pinfunction "51_51") (pintype "passive+no_connect"))
    )
    (net (code "105") (name "unconnected-(M1-PA2-Pad7)") (class "Default")
      (node (ref "M1") (pin "7") (pinfunction "PA2_7") (pintype "passive+no_connect"))
    )
    (net (code "106") (name "unconnected-(M1-PA3-Pad8)") (class "Default")
      (node (ref "M1") (pin "8") (pinfunction "PA3_8") (pintype "passive+no_connect"))
    )
    (net (code "107") (name "unconnected-(M1-PA4-Pad9)") (class "Default")
      (node (ref "M1") (pin "9") (pinfunction "PA4_9") (pintype "passive+no_connect"))
    )
    (net (code "108") (name "unconnected-(M1-PA5-Pad10)") (class "Default")
      (node (ref "M1") (pin "10") (pinfunction "PA5_10") (pintype "passive+no_connect"))
    )
    (net (code "109") (name "unconnected-(M1-PB11-Pad11)") (class "Default")
      (node (ref "M1") (pin "11") (pinfunction "PB11_11") (pintype "passive+no_connect"))
    )
    (net (code "110") (name "unconnected-(M1-PB13-Pad13)") (class "Default")
      (node (ref "M1") (pin "13") (pinfunction "PB13_13") (pintype "passive+no_connect"))
    )
    (net (code "111") (name "unconnected-(M1-PC6-Pad14)") (class "Default")
      (node (ref "M1") (pin "14") (pinfunction "PC6_14") (pintype "passive+no_connect"))
    )
    (net (code "112") (name "unconnected-(M1-PC7-Pad15)") (class "Default")
      (node (ref "M1") (pin "15") (pinfunction "PC7_15") (pintype "passive+no_connect"))
    )
    (net (code "113") (name "unconnected-(M1-PC8-Pad16)") (class "Default")
      (node (ref "M1") (pin "16") (pinfunction "PC8_16") (pintype "passive+no_connect"))
    )
    (net (code "114") (name "unconnected-(M1-PC9-Pad17)") (class "Default")
      (node (ref "M1") (pin "17") (pinfunction "PC9_17") (pintype "passive+no_connect"))
    )
    (net (code "115") (name "unconnected-(M1-PC10-Pad18)") (class "Default")
      (node (ref "M1") (pin "18") (pinfunction "PC10_18") (pintype "passive+no_connect"))
    )
    (net (code "116") (name "unconnected-(M1-PC11-Pad19)") (class "Default")
      (node (ref "M1") (pin "19") (pinfunction "PC11_19") (pintype "passive+no_connect"))
    )
    (net (code "117") (name "unconnected-(M1-PD13-Pad2)") (class "Default")
      (node (ref "M1") (pin "2") (pinfunction "PD13_2") (pintype "passive+no_connect"))
    )
    (net (code "118") (name "unconnected-(M1-PD14-Pad3)") (class "Default")
      (node (ref "M1") (pin "3") (pinfunction "PD14_3") (pintype "passive+no_connect"))
    )
    (net (code "119") (name "unconnected-(M1-PD15-Pad4)") (class "Default")
      (node (ref "M1") (pin "4") (pinfunction "PD15_4") (pintype "passive+no_connect"))
    )
    (net (code "120") (name "unconnected-(M1-PF4-Pad25)") (class "Default")
      (node (ref "M1") (pin "25") (pinfunction "PF4_25") (pintype "passive"))
    )
    (net (code "121") (name "unconnected-(M1-PF5-Pad26)") (class "Default")
      (node (ref "M1") (pin "26") (pinfunction "PF5_26") (pintype "passive"))
    )
    (net (code "122") (name "unconnected-(M1-PF6-Pad27)") (class "Default")
      (node (ref "M1") (pin "27") (pinfunction "PF6_27") (pintype "passive"))
    )
    (net (code "123") (name "unconnected-(M1-PF7-Pad28)") (class "Default")
      (node (ref "M1") (pin "28") (pinfunction "PF7_28") (pintype "passive"))
    )
    (net (code "124") (name "unconnected-(ON-Pad4)") (class "Default")
      (node (ref "ON") (pin "4") (pinfunction "4_4") (pintype "passive"))
    )
    (net (code "125") (name "unconnected-(RST-Pad4)") (class "Default")
      (node (ref "RST") (pin "4") (pinfunction "4_4") (pintype "passive"))
    )
    (net (code "126") (name "unconnected-(SP1-Pad1)") (class "Default")
      (node (ref "SP1") (pin "1") (pinfunction "1_1") (pintype "passive"))
    )
    (net (code "127") (name "unconnected-(SP2-Pad1)") (class "Default")
      (node (ref "SP2") (pin "1") (pinfunction "1_1") (pintype "passive"))
    )
    (net (code "128") (name "unconnected-(SP3-Pad1)") (class "Default")
      (node (ref "SP3") (pin "1") (pinfunction "1_1") (pintype "passive"))
    )
    (net (code "129") (name "unconnected-(SP4-Pad1)") (class "Default")
      (node (ref "SP4") (pin "1") (pinfunction "1_1") (pintype "passive"))
    )
    (net (code "130") (name "unconnected-(SP5-Pad1)") (class "Default")
      (node (ref "SP5") (pin "1") (pinfunction "1_1") (pintype "passive"))
    )
    (net (code "131") (name "unconnected-(WAKE-Pad4)") (class "Default")
      (node (ref "WAKE") (pin "4") (pinfunction "4_4") (pintype "passive"))
    )
  )
)
